# Config.net
KiCad netlist of a schematic drawn in Altium Designer
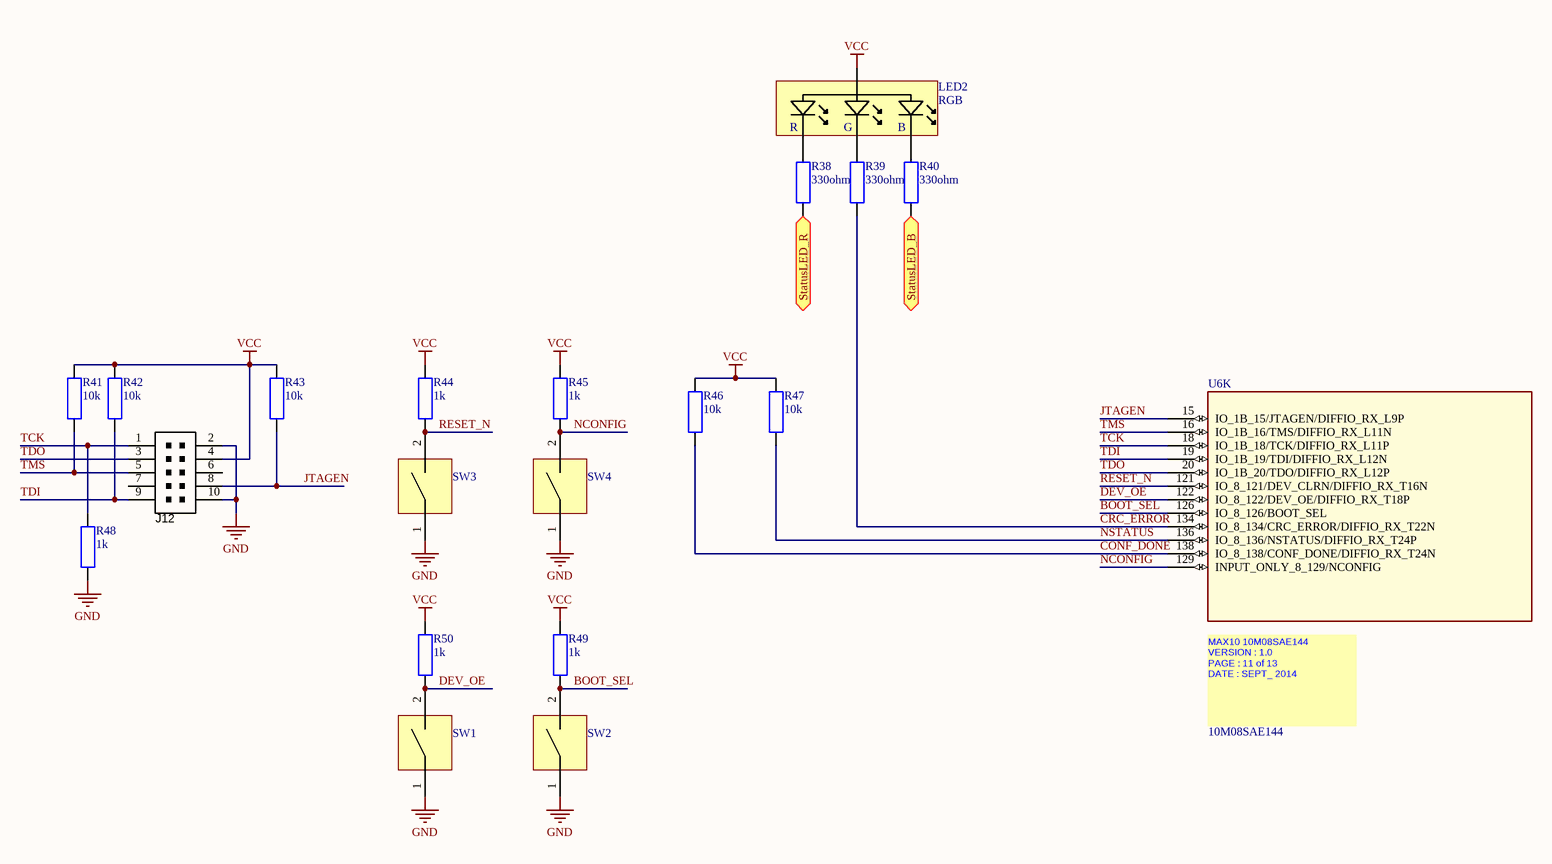
[diagram p0: Config.SchDoc]

(export (version "E")
  (design (tool "Eeschema 10.0.6"))
  (components
    (comp (ref "J12")
      (value "shrouded box header")
      (footprint "10P_PCB_HEADER_BRD_MNT")
      (description "Header THD 10 POS Double-row 2.54mm pitch")
      (libsource (lib "PBL - Connectors") (part "CONN_HEADER_2x5P_0.100in_Male"))
    )
    (comp (ref "LED2")
      (value "RGB")
      (footprint "ASMB-MTB1")
      (description "LED, HB, RGB, 0.09W, PLCC-4")
      (libsource (lib "CustomComponents") (part "ASMB-MTB1-0A3A2"))
    )
    (comp (ref "R38")
      (value "330ohm")
      (footprint "RESC1608X06L")
      (description "RES, THICK FILM, 330 OHM, 1%, 0.1W")
      (fields (field (name "Comment") "MCWR06X3300FTL"))
      (libsource (lib "CustomComponents") (part "MCWR06X3300FTL"))
    )
    (comp (ref "R39")
      (value "330ohm")
      (footprint "RESC1608X06L")
      (description "RES, THICK FILM, 330 OHM, 1%, 0.1W")
      (fields (field (name "Comment") "MCWR06X3300FTL"))
      (libsource (lib "CustomComponents") (part "MCWR06X3300FTL"))
    )
    (comp (ref "R40")
      (value "330ohm")
      (footprint "RESC1608X06L")
      (description "RES, THICK FILM, 330 OHM, 1%, 0.1W")
      (fields (field (name "Comment") "MCWR06X3300FTL"))
      (libsource (lib "CustomComponents") (part "MCWR06X3300FTL"))
    )
    (comp (ref "R41")
      (value "10k")
      (footprint "RESC1608X06L")
      (description "Resistor, 10k, 0603")
      (fields (field (name "Comment") "MCMR06X1002FTL"))
      (libsource (lib "CustomComponents") (part "MCMR06X1002FTL"))
    )
    (comp (ref "R42")
      (value "10k")
      (footprint "RESC1608X06L")
      (description "Resistor, 10k, 0603")
      (fields (field (name "Comment") "MCMR06X1002FTL"))
      (libsource (lib "CustomComponents") (part "MCMR06X1002FTL"))
    )
    (comp (ref "R43")
      (value "10k")
      (footprint "RESC1608X06L")
      (description "Resistor, 10k, 0603")
      (fields (field (name "Comment") "MCMR06X1002FTL"))
      (libsource (lib "CustomComponents") (part "MCMR06X1002FTL"))
    )
    (comp (ref "R44")
      (value "1k")
      (footprint "RESC1608X55N")
      (description "RESISTOR, CERAMIC, 1K, 0.1W, 1%")
      (fields (field (name "Comment") "MCMR06X1001FTL"))
      (libsource (lib "CustomComponents") (part "MCMR06X1001FTL"))
    )
    (comp (ref "R45")
      (value "1k")
      (footprint "RESC1608X55N")
      (description "RESISTOR, CERAMIC, 1K, 0.1W, 1%")
      (fields (field (name "Comment") "MCMR06X1001FTL"))
      (libsource (lib "CustomComponents") (part "MCMR06X1001FTL"))
    )
    (comp (ref "R46")
      (value "10k")
      (footprint "RESC1608X06L")
      (description "Resistor, 10k, 0603")
      (fields (field (name "Comment") "MCMR06X1002FTL"))
      (libsource (lib "CustomComponents") (part "MCMR06X1002FTL"))
    )
    (comp (ref "R47")
      (value "10k")
      (footprint "RESC1608X06L")
      (description "Resistor, 10k, 0603")
      (fields (field (name "Comment") "MCMR06X1002FTL"))
      (libsource (lib "CustomComponents") (part "MCMR06X1002FTL"))
    )
    (comp (ref "R48")
      (value "1k")
      (footprint "RESC1608X55N")
      (description "RESISTOR, CERAMIC, 1K, 0.1W, 1%")
      (fields (field (name "Comment") "MCMR06X1001FTL"))
      (libsource (lib "CustomComponents") (part "MCMR06X1001FTL"))
    )
    (comp (ref "R49")
      (value "1k")
      (footprint "RESC1608X55N")
      (description "RESISTOR, CERAMIC, 1K, 0.1W, 1%")
      (fields (field (name "Comment") "MCMR06X1001FTL"))
      (libsource (lib "CustomComponents") (part "MCMR06X1001FTL"))
    )
    (comp (ref "R50")
      (value "1k")
      (footprint "RESC1608X55N")
      (description "RESISTOR, CERAMIC, 1K, 0.1W, 1%")
      (fields (field (name "Comment") "MCMR06X1001FTL"))
      (libsource (lib "CustomComponents") (part "MCMR06X1001FTL"))
    )
    (comp (ref "SW1")
      (value "FSM4JH")
      (footprint "FSM4JH")
      (description "SWITCH, SPNO, 0.05A")
      (libsource (lib "CustomComponents") (part "FSM4JH"))
    )
    (comp (ref "SW2")
      (value "FSM4JH")
      (footprint "FSM4JH")
      (description "SWITCH, SPNO, 0.05A")
      (libsource (lib "CustomComponents") (part "FSM4JH"))
    )
    (comp (ref "SW3")
      (value "FSM4JH")
      (footprint "FSM4JH")
      (description "SWITCH, SPNO, 0.05A")
      (libsource (lib "CustomComponents") (part "FSM4JH"))
    )
    (comp (ref "SW4")
      (value "FSM4JH")
      (footprint "FSM4JH")
      (description "SWITCH, SPNO, 0.05A")
      (libsource (lib "CustomComponents") (part "FSM4JH"))
    )
    (comp (ref "U6")
      (value "10M08SAE144")
      (footprint "SQFP50P2200X2200X165_HS-145N")
      (libsource (lib "10M08SAREVERSIONTEST_Library") (part "10M08SAE144"))
    )
  )
  (nets
    (net (code "1") (name "/BOOT_SEL") (class "Default")
      (node (ref "R49") (pin "1") (pinfunction "0_1") (pintype "passive"))
      (node (ref "SW2") (pin "2") (pinfunction "2_2") (pintype "passive"))
      (node (ref "U6") (pin "126") (pinfunction "IO_8_126/BOOT_SEL_126") (pintype "bidirectional"))
    )
    (net (code "2") (name "/CONF_DONE") (class "Default")
      (node (ref "R46") (pin "1") (pinfunction "0_1") (pintype "passive"))
      (node (ref "U6") (pin "138") (pinfunction "IO_8_138/CONF_DONE/DIFFIO_RX_T24N_138") (pintype "bidirectional"))
    )
    (net (code "3") (name "/CRC_ERROR") (class "Default")
      (node (ref "R39") (pin "2") (pinfunction "0_2") (pintype "passive"))
      (node (ref "U6") (pin "134") (pinfunction "IO_8_134/CRC_ERROR/DIFFIO_RX_T22N_134") (pintype "bidirectional"))
    )
    (net (code "4") (name "/DEV_OE") (class "Default")
      (node (ref "R50") (pin "1") (pinfunction "0_1") (pintype "passive"))
      (node (ref "SW1") (pin "2") (pinfunction "2_2") (pintype "passive"))
      (node (ref "U6") (pin "122") (pinfunction "IO_8_122/DEV_OE/DIFFIO_RX_T18P_122") (pintype "bidirectional"))
    )
    (net (code "5") (name "/JTAGEN") (class "Default")
      (node (ref "J12") (pin "8") (pinfunction "8_8") (pintype "passive"))
      (node (ref "R43") (pin "1") (pinfunction "0_1") (pintype "passive"))
      (node (ref "U6") (pin "15") (pinfunction "IO_1B_15/JTAGEN/DIFFIO_RX_L9P_15") (pintype "bidirectional"))
    )
    (net (code "6") (name "/NCONFIG") (class "Default")
      (node (ref "R45") (pin "1") (pinfunction "0_1") (pintype "passive"))
      (node (ref "SW4") (pin "2") (pinfunction "2_2") (pintype "passive"))
      (node (ref "U6") (pin "129") (pinfunction "INPUT_ONLY_8_129/NCONFIG_129") (pintype "bidirectional"))
    )
    (net (code "7") (name "/NSTATUS") (class "Default")
      (node (ref "R47") (pin "1") (pinfunction "0_1") (pintype "passive"))
      (node (ref "U6") (pin "136") (pinfunction "IO_8_136/NSTATUS/DIFFIO_RX_T24P_136") (pintype "bidirectional"))
    )
    (net (code "8") (name "/RESET_N") (class "Default")
      (node (ref "R44") (pin "1") (pinfunction "0_1") (pintype "passive"))
      (node (ref "SW3") (pin "2") (pinfunction "2_2") (pintype "passive"))
      (node (ref "U6") (pin "121") (pinfunction "IO_8_121/DEV_CLRN/DIFFIO_RX_T16N_121") (pintype "bidirectional"))
    )
    (net (code "9") (name "/StatusLED_B") (class "Default")
      (node (ref "R40") (pin "2") (pinfunction "0_2") (pintype "passive"))
    )
    (net (code "10") (name "/StatusLED_R") (class "Default")
      (node (ref "R38") (pin "2") (pinfunction "0_2") (pintype "passive"))
    )
    (net (code "11") (name "/TCK") (class "Default")
      (node (ref "J12") (pin "1") (pinfunction "1_1") (pintype "passive"))
      (node (ref "R48") (pin "2") (pinfunction "0_2") (pintype "passive"))
      (node (ref "U6") (pin "18") (pinfunction "IO_1B_18/TCK/DIFFIO_RX_L11P_18") (pintype "bidirectional"))
    )
    (net (code "12") (name "/TDI") (class "Default")
      (node (ref "J12") (pin "9") (pinfunction "9_9") (pintype "passive"))
      (node (ref "R42") (pin "1") (pinfunction "0_1") (pintype "passive"))
      (node (ref "U6") (pin "19") (pinfunction "IO_1B_19/TDI/DIFFIO_RX_L12N_19") (pintype "bidirectional"))
    )
    (net (code "13") (name "/TDO") (class "Default")
      (node (ref "J12") (pin "3") (pinfunction "3_3") (pintype "passive"))
      (node (ref "U6") (pin "20") (pinfunction "IO_1B_20/TDO/DIFFIO_RX_L12P_20") (pintype "bidirectional"))
    )
    (net (code "14") (name "/TMS") (class "Default")
      (node (ref "J12") (pin "5") (pinfunction "5_5") (pintype "passive"))
      (node (ref "R41") (pin "1") (pinfunction "0_1") (pintype "passive"))
      (node (ref "U6") (pin "16") (pinfunction "IO_1B_16/TMS/DIFFIO_RX_L11N_16") (pintype "bidirectional"))
    )
    (net (code "15") (name "GND") (class "Default")
      (node (ref "J12") (pin "10") (pinfunction "10_10") (pintype "passive"))
      (node (ref "J12") (pin "2") (pinfunction "2_2") (pintype "passive"))
      (node (ref "R48") (pin "1") (pinfunction "0_1") (pintype "passive"))
      (node (ref "SW1") (pin "1") (pinfunction "1_1") (pintype "passive"))
      (node (ref "SW2") (pin "1") (pinfunction "1_1") (pintype "passive"))
      (node (ref "SW3") (pin "1") (pinfunction "1_1") (pintype "passive"))
      (node (ref "SW4") (pin "1") (pinfunction "1_1") (pintype "passive"))
    )
    (net (code "16") (name "Net-(LED2-B)") (class "Default")
      (node (ref "LED2") (pin "3") (pinfunction "B_3") (pintype "passive"))
      (node (ref "R40") (pin "1") (pinfunction "0_1") (pintype "passive"))
    )
    (net (code "17") (name "Net-(LED2-G)") (class "Default")
      (node (ref "LED2") (pin "2") (pinfunction "G_2") (pintype "passive"))
      (node (ref "R39") (pin "1") (pinfunction "0_1") (pintype "passive"))
    )
    (net (code "18") (name "Net-(LED2-R)") (class "Default")
      (node (ref "LED2") (pin "1") (pinfunction "R_1") (pintype "passive"))
      (node (ref "R38") (pin "1") (pinfunction "0_1") (pintype "passive"))
    )
    (net (code "19") (name "VCC") (class "Default")
      (node (ref "J12") (pin "4") (pinfunction "4_4") (pintype "passive"))
      (node (ref "LED2") (pin "4") (pinfunction "A_4") (pintype "passive"))
      (node (ref "R41") (pin "2") (pinfunction "0_2") (pintype "passive"))
      (node (ref "R42") (pin "2") (pinfunction "0_2") (pintype "passive"))
      (node (ref "R43") (pin "2") (pinfunction "0_2") (pintype "passive"))
      (node (ref "R44") (pin "2") (pinfunction "0_2") (pintype "passive"))
      (node (ref "R45") (pin "2") (pinfunction "0_2") (pintype "passive"))
      (node (ref "R46") (pin "2") (pinfunction "0_2") (pintype "passive"))
      (node (ref "R47") (pin "2") (pinfunction "0_2") (pintype "passive"))
      (node (ref "R49") (pin "2") (pinfunction "0_2") (pintype "passive"))
      (node (ref "R50") (pin "2") (pinfunction "0_2") (pintype "passive"))
    )
    (net (code "20") (name "unconnected-(J12-Pad6)") (class "Default")
      (node (ref "J12") (pin "6") (pinfunction "6_6") (pintype "passive"))
    )
    (net (code "21") (name "unconnected-(J12-Pad7)") (class "Default")
      (node (ref "J12") (pin "7") (pinfunction "7_7") (pintype "passive"))
    )
  )
)
